# ENCODER_BUFFER.net
KiCad netlist of a schematic drawn in EAGLE
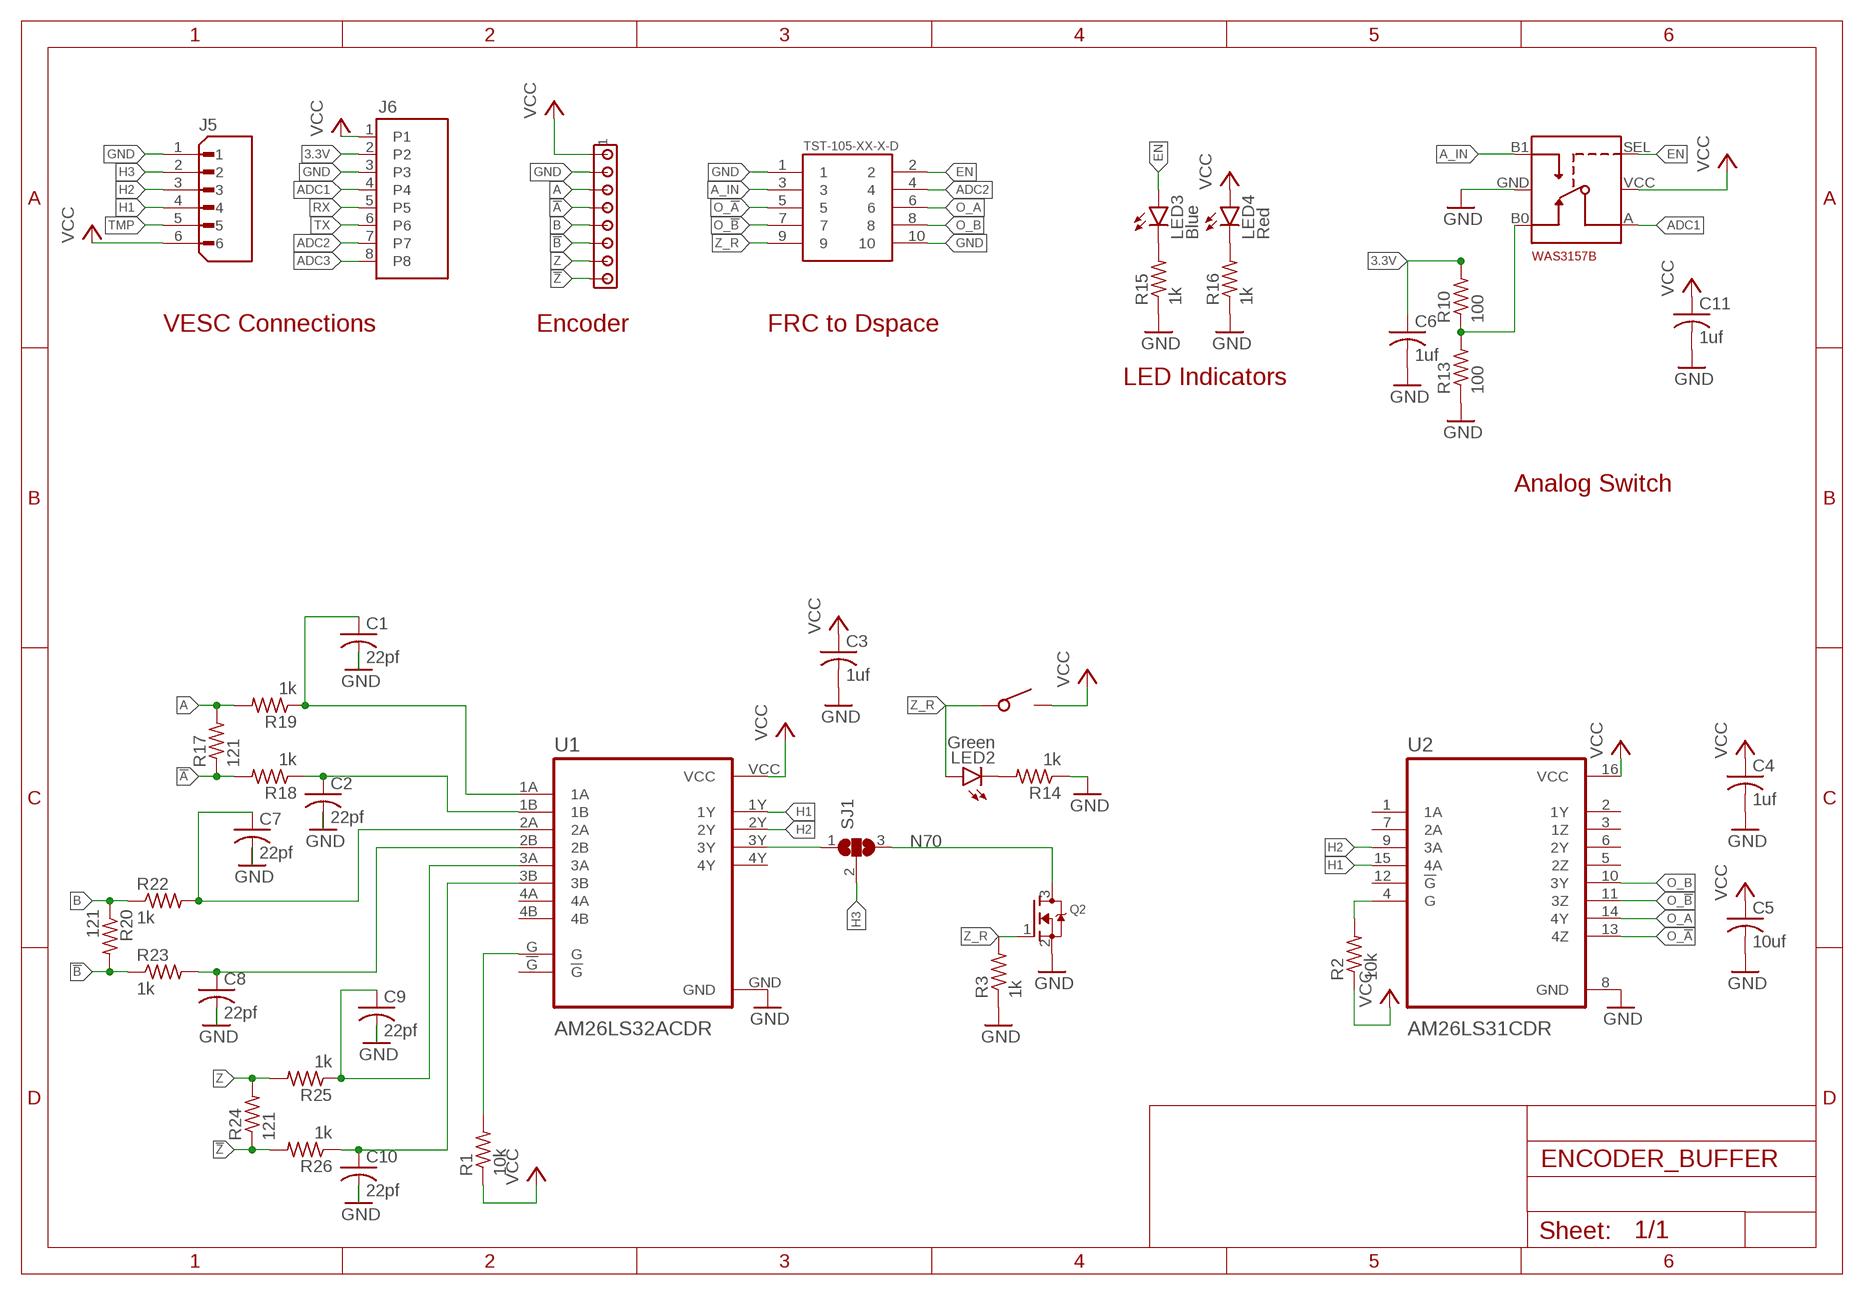
[diagram p0: schematic, sheet 1]

(export (version "E")
  (design (tool "Eeschema 10.0.6"))
  (components
    (comp (ref "C1")
      (value "22pf")
      (footprint "eagle-import:C0402")
      (libsource (lib "eagle-import") (part "C-USC0402"))
    )
    (comp (ref "C2")
      (value "22pf")
      (footprint "eagle-import:C0402")
      (libsource (lib "eagle-import") (part "C-USC0402"))
    )
    (comp (ref "C3")
      (value "1uf")
      (footprint "eagle-import:C0402")
      (libsource (lib "eagle-import") (part "C-USC0402"))
    )
    (comp (ref "C4")
      (value "1uf")
      (footprint "eagle-import:C0402")
      (libsource (lib "eagle-import") (part "C-USC0402"))
    )
    (comp (ref "C5")
      (value "10uf")
      (footprint "eagle-import:C0402")
      (libsource (lib "eagle-import") (part "C-USC0402"))
    )
    (comp (ref "C6")
      (value "1uf")
      (footprint "eagle-import:C0402")
      (libsource (lib "eagle-import") (part "C-USC0402"))
    )
    (comp (ref "C7")
      (value "22pf")
      (footprint "eagle-import:C0402")
      (libsource (lib "eagle-import") (part "C-USC0402"))
    )
    (comp (ref "C8")
      (value "22pf")
      (footprint "eagle-import:C0402")
      (libsource (lib "eagle-import") (part "C-USC0402"))
    )
    (comp (ref "C9")
      (value "22pf")
      (footprint "eagle-import:C0402")
      (libsource (lib "eagle-import") (part "C-USC0402"))
    )
    (comp (ref "C10")
      (value "22pf")
      (footprint "eagle-import:C0402")
      (libsource (lib "eagle-import") (part "C-USC0402"))
    )
    (comp (ref "C11")
      (value "1uf")
      (footprint "eagle-import:C0402")
      (libsource (lib "eagle-import") (part "C-USC0402"))
    )
    (comp (ref "J2")
      (value "TST-105-XX-X-D")
      (footprint "eagle-import:TST-105-XX-X-D")
      (fields (field (name "MF") "Samtec") (field (name "MP") "TST-105-03-S-D"))
      (libsource (lib "eagle-import") (part "TST-105-XX-X-D"))
    )
    (comp (ref "J3")
      (value "MTA08-100")
      (footprint "eagle-import:10X08MTA")
      (libsource (lib "eagle-import") (part "MTA08-100"))
    )
    (comp (ref "J5")
      (value "B6B-PH-K-S(LF)(SN)")
      (footprint "eagle-import:JST_B6B-PH-K-S(LF)(SN)")
      (fields (field (name "MF") "JST Sales"))
      (libsource (lib "eagle-import") (part "B6B-PH-K-S(LF)(SN)"))
    )
    (comp (ref "J6")
      (value "B8B-PH-K-S(LF)(SN)")
      (footprint "eagle-import:JST_B8B-PH-K-S(LF)(SN)")
      (fields (field (name "MF") "JST Sales"))
      (libsource (lib "eagle-import") (part "B8B-PH-K-S(LF)(SN)"))
    )
    (comp (ref "LED2")
      (value "Green")
      (footprint "eagle-import:CHIPLED_0603")
      (libsource (lib "eagle-import") (part "LEDCHIPLED_0603"))
    )
    (comp (ref "LED3")
      (value "Blue")
      (footprint "eagle-import:CHIPLED_0603")
      (libsource (lib "eagle-import") (part "LEDCHIPLED_0603"))
    )
    (comp (ref "LED4")
      (value "Red")
      (footprint "eagle-import:CHIPLED_0603")
      (libsource (lib "eagle-import") (part "LEDCHIPLED_0603"))
    )
    (comp (ref "Q2")
      (value "MOSFET-NREFLOW")
      (footprint "eagle-import:SOT23")
      (libsource (lib "eagle-import") (part "MOSFET-NREFLOW"))
    )
    (comp (ref "R1")
      (value "10k")
      (footprint "eagle-import:R0402")
      (libsource (lib "eagle-import") (part "R-US_R0402"))
    )
    (comp (ref "R2")
      (value "10k")
      (footprint "eagle-import:R0402")
      (libsource (lib "eagle-import") (part "R-US_R0402"))
    )
    (comp (ref "R3")
      (value "1k")
      (footprint "eagle-import:R0402")
      (libsource (lib "eagle-import") (part "R-US_R0402"))
    )
    (comp (ref "R10")
      (value "100")
      (footprint "eagle-import:R0402")
      (libsource (lib "eagle-import") (part "R-US_R0402"))
    )
    (comp (ref "R13")
      (value "100")
      (footprint "eagle-import:R0402")
      (libsource (lib "eagle-import") (part "R-US_R0402"))
    )
    (comp (ref "R14")
      (value "1k")
      (footprint "eagle-import:R0402")
      (libsource (lib "eagle-import") (part "R-US_R0402"))
    )
    (comp (ref "R15")
      (value "1k")
      (footprint "eagle-import:R0402")
      (libsource (lib "eagle-import") (part "R-US_R0402"))
    )
    (comp (ref "R16")
      (value "1k")
      (footprint "eagle-import:R0402")
      (libsource (lib "eagle-import") (part "R-US_R0402"))
    )
    (comp (ref "R17")
      (value "121")
      (footprint "eagle-import:R0402")
      (libsource (lib "eagle-import") (part "R-US_R0402"))
    )
    (comp (ref "R18")
      (value "1k")
      (footprint "eagle-import:R0402")
      (libsource (lib "eagle-import") (part "R-US_R0402"))
    )
    (comp (ref "R19")
      (value "1k")
      (footprint "eagle-import:R0402")
      (libsource (lib "eagle-import") (part "R-US_R0402"))
    )
    (comp (ref "R20")
      (value "121")
      (footprint "eagle-import:R0402")
      (libsource (lib "eagle-import") (part "R-US_R0402"))
    )
    (comp (ref "R22")
      (value "1k")
      (footprint "eagle-import:R0402")
      (libsource (lib "eagle-import") (part "R-US_R0402"))
    )
    (comp (ref "R23")
      (value "1k")
      (footprint "eagle-import:R0402")
      (libsource (lib "eagle-import") (part "R-US_R0402"))
    )
    (comp (ref "R24")
      (value "121")
      (footprint "eagle-import:R0402")
      (libsource (lib "eagle-import") (part "R-US_R0402"))
    )
    (comp (ref "R25")
      (value "1k")
      (footprint "eagle-import:R0402")
      (libsource (lib "eagle-import") (part "R-US_R0402"))
    )
    (comp (ref "R26")
      (value "1k")
      (footprint "eagle-import:R0402")
      (libsource (lib "eagle-import") (part "R-US_R0402"))
    )
    (comp (ref "SJ1")
      (value "SJ2W")
      (footprint "eagle-import:SJ_2")
      (libsource (lib "eagle-import") (part "SJ2W"))
    )
    (comp (ref "U$1")
      (value "TS-1088-AR02016")
      (footprint "eagle-import:SMD")
      (libsource (lib "eagle-import") (part "TS-1088-AR02016"))
    )
    (comp (ref "U1")
      (value "AM26LS32ACDR")
      (footprint "eagle-import:SOIC127P600X175-16N")
      (fields (field (name "MF") "Texas Instruments") (field (name "MP") "AM26LS31CDR"))
      (libsource (lib "eagle-import") (part "AM26LS32ACDR"))
    )
    (comp (ref "U2")
      (value "AM26LS31CDR")
      (footprint "eagle-import:SOIC127P600X175-16N")
      (fields (field (name "MF") "Texas Instruments"))
      (libsource (lib "eagle-import") (part "AM26LS31CDR"))
    )
    (comp (ref "U3")
      (value "WAS3157BUMT6")
      (footprint "eagle-import:UMT6")
      (fields (field (name "MF") "Rohm") (field (name "MP") "UMH3N"))
      (libsource (lib "eagle-import") (part "WAS3157BUMT6"))
    )
  )
  (nets
    (net (code "1") (name "/N70") (class "Default")
      (node (ref "Q2") (pin "3") (pinfunction "D_3") (pintype "bidirectional"))
      (node (ref "SJ1") (pin "3") (pinfunction "3_3") (pintype "passive"))
    )
    (net (code "2") (name "/O_~{A}") (class "Default")
      (node (ref "J2") (pin "5") (pinfunction "5_5") (pintype "bidirectional"))
      (node (ref "U2") (pin "13") (pinfunction "4Z_13") (pintype "output"))
    )
    (net (code "3") (name "/O_~{B}") (class "Default")
      (node (ref "J2") (pin "7") (pinfunction "7_7") (pintype "bidirectional"))
      (node (ref "U2") (pin "11") (pinfunction "3Z_11") (pintype "output"))
    )
    (net (code "4") (name "/~{A}") (class "Default")
      (node (ref "J3") (pin "4") (pinfunction "4_4") (pintype "passive"))
      (node (ref "R17") (pin "1") (pinfunction "1_1") (pintype "passive"))
      (node (ref "R18") (pin "2") (pinfunction "2_2") (pintype "passive"))
    )
    (net (code "5") (name "/~{B}") (class "Default")
      (node (ref "J3") (pin "6") (pinfunction "6_6") (pintype "passive"))
      (node (ref "R20") (pin "2") (pinfunction "2_2") (pintype "passive"))
      (node (ref "R23") (pin "1") (pinfunction "1_1") (pintype "passive"))
    )
    (net (code "6") (name "/~{Z}") (class "Default")
      (node (ref "J3") (pin "8") (pinfunction "8_8") (pintype "passive"))
      (node (ref "R24") (pin "1") (pinfunction "1_1") (pintype "passive"))
      (node (ref "R26") (pin "2") (pinfunction "2_2") (pintype "passive"))
    )
    (net (code "7") (name "3.3V") (class "Default")
      (node (ref "C6") (pin "1") (pinfunction "1_1") (pintype "passive"))
      (node (ref "J6") (pin "2") (pinfunction "P2_2") (pintype "passive"))
      (node (ref "R10") (pin "2") (pinfunction "2_2") (pintype "passive"))
    )
    (net (code "8") (name "A") (class "Default")
      (node (ref "J3") (pin "3") (pinfunction "3_3") (pintype "passive"))
      (node (ref "R17") (pin "2") (pinfunction "2_2") (pintype "passive"))
      (node (ref "R19") (pin "2") (pinfunction "2_2") (pintype "passive"))
    )
    (net (code "9") (name "ADC1") (class "Default")
      (node (ref "J6") (pin "4") (pinfunction "P4_4") (pintype "passive"))
      (node (ref "U3") (pin "A") (pinfunction "A_A") (pintype "output"))
    )
    (net (code "10") (name "ADC2") (class "Default")
      (node (ref "J2") (pin "4") (pinfunction "4_4") (pintype "bidirectional"))
      (node (ref "J6") (pin "7") (pinfunction "P7_7") (pintype "passive"))
    )
    (net (code "11") (name "ADC3") (class "Default")
      (node (ref "J6") (pin "8") (pinfunction "P8_8") (pintype "passive"))
    )
    (net (code "12") (name "A_IN") (class "Default")
      (node (ref "J2") (pin "3") (pinfunction "3_3") (pintype "bidirectional"))
      (node (ref "U3") (pin "B1") (pinfunction "B1_B1") (pintype "output"))
    )
    (net (code "13") (name "B") (class "Default")
      (node (ref "J3") (pin "5") (pinfunction "5_5") (pintype "passive"))
      (node (ref "R20") (pin "1") (pinfunction "1_1") (pintype "passive"))
      (node (ref "R22") (pin "1") (pinfunction "1_1") (pintype "passive"))
    )
    (net (code "14") (name "EN") (class "Default")
      (node (ref "J2") (pin "2") (pinfunction "2_2") (pintype "bidirectional"))
      (node (ref "LED3") (pin "A") (pinfunction "A_A") (pintype "passive"))
      (node (ref "U3") (pin "SEL") (pinfunction "SEL_SEL") (pintype "input"))
    )
    (net (code "15") (name "GND") (class "Default")
      (node (ref "C1") (pin "2") (pinfunction "2_2") (pintype "passive"))
      (node (ref "C10") (pin "2") (pinfunction "2_2") (pintype "passive"))
      (node (ref "C11") (pin "2") (pinfunction "2_2") (pintype "passive"))
      (node (ref "C2") (pin "2") (pinfunction "2_2") (pintype "passive"))
      (node (ref "C3") (pin "2") (pinfunction "2_2") (pintype "passive"))
      (node (ref "C4") (pin "2") (pinfunction "2_2") (pintype "passive"))
      (node (ref "C5") (pin "2") (pinfunction "2_2") (pintype "passive"))
      (node (ref "C6") (pin "2") (pinfunction "2_2") (pintype "passive"))
      (node (ref "C7") (pin "2") (pinfunction "2_2") (pintype "passive"))
      (node (ref "C8") (pin "2") (pinfunction "2_2") (pintype "passive"))
      (node (ref "C9") (pin "2") (pinfunction "2_2") (pintype "passive"))
      (node (ref "J2") (pin "1") (pinfunction "1_1") (pintype "bidirectional"))
      (node (ref "J2") (pin "10") (pinfunction "10_10") (pintype "bidirectional"))
      (node (ref "J3") (pin "2") (pinfunction "2_2") (pintype "passive"))
      (node (ref "J5") (pin "1") (pinfunction "1_1") (pintype "passive"))
      (node (ref "J6") (pin "3") (pinfunction "P3_3") (pintype "passive"))
      (node (ref "Q2") (pin "2") (pinfunction "S_2") (pintype "bidirectional"))
      (node (ref "R13") (pin "1") (pinfunction "1_1") (pintype "passive"))
      (node (ref "R14") (pin "1") (pinfunction "1_1") (pintype "passive"))
      (node (ref "R15") (pin "1") (pinfunction "1_1") (pintype "passive"))
      (node (ref "R16") (pin "1") (pinfunction "1_1") (pintype "passive"))
      (node (ref "R3") (pin "1") (pinfunction "1_1") (pintype "passive"))
      (node (ref "U1") (pin "GND") (pinfunction "GND_GND") (pintype "power_in"))
      (node (ref "U2") (pin "8") (pinfunction "GND_8") (pintype "power_in"))
      (node (ref "U3") (pin "GND") (pinfunction "GND_GND") (pintype "input"))
    )
    (net (code "16") (name "H1") (class "Default")
      (node (ref "J5") (pin "4") (pinfunction "4_4") (pintype "passive"))
      (node (ref "U1") (pin "1Y") (pinfunction "1Y_1Y") (pintype "bidirectional"))
      (node (ref "U2") (pin "15") (pinfunction "4A_15") (pintype "input"))
    )
    (net (code "17") (name "H2") (class "Default")
      (node (ref "J5") (pin "3") (pinfunction "3_3") (pintype "passive"))
      (node (ref "U1") (pin "2Y") (pinfunction "2Y_2Y") (pintype "bidirectional"))
      (node (ref "U2") (pin "9") (pinfunction "3A_9") (pintype "input"))
    )
    (net (code "18") (name "H3") (class "Default")
      (node (ref "J5") (pin "2") (pinfunction "2_2") (pintype "passive"))
      (node (ref "SJ1") (pin "2") (pinfunction "2_2") (pintype "passive"))
    )
    (net (code "19") (name "Net-(C1-Pad1)") (class "Default")
      (node (ref "C1") (pin "1") (pinfunction "1_1") (pintype "passive"))
      (node (ref "R19") (pin "1") (pinfunction "1_1") (pintype "passive"))
      (node (ref "U1") (pin "1A") (pinfunction "1A_1A") (pintype "bidirectional"))
    )
    (net (code "20") (name "Net-(C2-Pad1)") (class "Default")
      (node (ref "C2") (pin "1") (pinfunction "1_1") (pintype "passive"))
      (node (ref "R18") (pin "1") (pinfunction "1_1") (pintype "passive"))
      (node (ref "U1") (pin "1B") (pinfunction "1B_1B") (pintype "bidirectional"))
    )
    (net (code "21") (name "Net-(C7-Pad1)") (class "Default")
      (node (ref "C7") (pin "1") (pinfunction "1_1") (pintype "passive"))
      (node (ref "R22") (pin "2") (pinfunction "2_2") (pintype "passive"))
      (node (ref "U1") (pin "2A") (pinfunction "2A_2A") (pintype "bidirectional"))
    )
    (net (code "22") (name "Net-(C8-Pad1)") (class "Default")
      (node (ref "C8") (pin "1") (pinfunction "1_1") (pintype "passive"))
      (node (ref "R23") (pin "2") (pinfunction "2_2") (pintype "passive"))
      (node (ref "U1") (pin "2B") (pinfunction "2B_2B") (pintype "bidirectional"))
    )
    (net (code "23") (name "Net-(C9-Pad1)") (class "Default")
      (node (ref "C9") (pin "1") (pinfunction "1_1") (pintype "passive"))
      (node (ref "R25") (pin "1") (pinfunction "1_1") (pintype "passive"))
      (node (ref "U1") (pin "3A") (pinfunction "3A_3A") (pintype "bidirectional"))
    )
    (net (code "24") (name "Net-(C10-Pad1)") (class "Default")
      (node (ref "C10") (pin "1") (pinfunction "1_1") (pintype "passive"))
      (node (ref "R26") (pin "1") (pinfunction "1_1") (pintype "passive"))
      (node (ref "U1") (pin "3B") (pinfunction "3B_3B") (pintype "bidirectional"))
    )
    (net (code "25") (name "Net-(LED2-PadC)") (class "Default")
      (node (ref "LED2") (pin "C") (pinfunction "C_C") (pintype "passive"))
      (node (ref "R14") (pin "2") (pinfunction "2_2") (pintype "passive"))
    )
    (net (code "26") (name "Net-(LED3-PadC)") (class "Default")
      (node (ref "LED3") (pin "C") (pinfunction "C_C") (pintype "passive"))
      (node (ref "R15") (pin "2") (pinfunction "2_2") (pintype "passive"))
    )
    (net (code "27") (name "Net-(LED4-PadC)") (class "Default")
      (node (ref "LED4") (pin "C") (pinfunction "C_C") (pintype "passive"))
      (node (ref "R16") (pin "2") (pinfunction "2_2") (pintype "passive"))
    )
    (net (code "28") (name "Net-(R1-Pad2)") (class "Default")
      (node (ref "R1") (pin "2") (pinfunction "2_2") (pintype "passive"))
      (node (ref "U1") (pin "G") (pinfunction "G_G") (pintype "input"))
    )
    (net (code "29") (name "Net-(R10-Pad1)") (class "Default")
      (node (ref "R10") (pin "1") (pinfunction "1_1") (pintype "passive"))
      (node (ref "R13") (pin "2") (pinfunction "2_2") (pintype "passive"))
      (node (ref "U3") (pin "B0") (pinfunction "B0_B0") (pintype "input"))
    )
    (net (code "30") (name "Net-(SJ1-Pad1)") (class "Default")
      (node (ref "SJ1") (pin "1") (pinfunction "1_1") (pintype "passive"))
      (node (ref "U1") (pin "3Y") (pinfunction "3Y_3Y") (pintype "bidirectional"))
    )
    (net (code "31") (name "Net-(U2-G)") (class "Default")
      (node (ref "R2") (pin "2") (pinfunction "2_2") (pintype "passive"))
      (node (ref "U2") (pin "4") (pinfunction "G_4") (pintype "input"))
    )
    (net (code "32") (name "O_A") (class "Default")
      (node (ref "J2") (pin "6") (pinfunction "6_6") (pintype "bidirectional"))
      (node (ref "U2") (pin "14") (pinfunction "4Y_14") (pintype "output"))
    )
    (net (code "33") (name "O_B") (class "Default")
      (node (ref "J2") (pin "8") (pinfunction "8_8") (pintype "bidirectional"))
      (node (ref "U2") (pin "10") (pinfunction "3Y_10") (pintype "output"))
    )
    (net (code "34") (name "RX") (class "Default")
      (node (ref "J6") (pin "5") (pinfunction "P5_5") (pintype "passive"))
    )
    (net (code "35") (name "TMP") (class "Default")
      (node (ref "J5") (pin "5") (pinfunction "5_5") (pintype "passive"))
    )
    (net (code "36") (name "TX") (class "Default")
      (node (ref "J6") (pin "6") (pinfunction "P6_6") (pintype "passive"))
    )
    (net (code "37") (name "VCC") (class "Default")
      (node (ref "C11") (pin "1") (pinfunction "1_1") (pintype "passive"))
      (node (ref "C3") (pin "1") (pinfunction "1_1") (pintype "passive"))
      (node (ref "C4") (pin "1") (pinfunction "1_1") (pintype "passive"))
      (node (ref "C5") (pin "1") (pinfunction "1_1") (pintype "passive"))
      (node (ref "J3") (pin "1") (pinfunction "1_1") (pintype "passive"))
      (node (ref "J5") (pin "6") (pinfunction "6_6") (pintype "passive"))
      (node (ref "J6") (pin "1") (pinfunction "P1_1") (pintype "passive"))
      (node (ref "LED4") (pin "A") (pinfunction "A_A") (pintype "passive"))
      (node (ref "R1") (pin "1") (pinfunction "1_1") (pintype "passive"))
      (node (ref "R2") (pin "1") (pinfunction "1_1") (pintype "passive"))
      (node (ref "U$1") (pin "P$2") (pinfunction "P$2_P$2") (pintype "bidirectional"))
      (node (ref "U1") (pin "VCC") (pinfunction "VCC_VCC") (pintype "power_in"))
      (node (ref "U2") (pin "16") (pinfunction "VCC_16") (pintype "power_in"))
      (node (ref "U3") (pin "VCC") (pinfunction "VCC_VCC") (pintype "input"))
    )
    (net (code "38") (name "Z") (class "Default")
      (node (ref "J3") (pin "7") (pinfunction "7_7") (pintype "passive"))
      (node (ref "R24") (pin "2") (pinfunction "2_2") (pintype "passive"))
      (node (ref "R25") (pin "2") (pinfunction "2_2") (pintype "passive"))
    )
    (net (code "39") (name "Z_R") (class "Default")
      (node (ref "J2") (pin "9") (pinfunction "9_9") (pintype "bidirectional"))
      (node (ref "LED2") (pin "A") (pinfunction "A_A") (pintype "passive"))
      (node (ref "Q2") (pin "1") (pinfunction "G_1") (pintype "bidirectional"))
      (node (ref "R3") (pin "2") (pinfunction "2_2") (pintype "passive"))
      (node (ref "U$1") (pin "P$1") (pinfunction "P$1_P$1") (pintype "bidirectional"))
    )
    (net (code "40") (name "unconnected-(U1-Pad4A)") (class "Default")
      (node (ref "U1") (pin "4A") (pinfunction "4A_4A") (pintype "bidirectional"))
    )
    (net (code "41") (name "unconnected-(U1-Pad4B)") (class "Default")
      (node (ref "U1") (pin "4B") (pinfunction "4B_4B") (pintype "bidirectional"))
    )
    (net (code "42") (name "unconnected-(U1-Pad4Y)") (class "Default")
      (node (ref "U1") (pin "4Y") (pinfunction "4Y_4Y") (pintype "bidirectional"))
    )
    (net (code "43") (name "unconnected-(U1-~{G}-Pad!G)") (class "Default")
      (node (ref "U1") (pin "!G") (pinfunction "~{G}_!G") (pintype "input"))
    )
    (net (code "44") (name "unconnected-(U2-1A-Pad1)") (class "Default")
      (node (ref "U2") (pin "1") (pinfunction "1A_1") (pintype "input"))
    )
    (net (code "45") (name "unconnected-(U2-1Y-Pad2)") (class "Default")
      (node (ref "U2") (pin "2") (pinfunction "1Y_2") (pintype "output"))
    )
    (net (code "46") (name "unconnected-(U2-1Z-Pad3)") (class "Default")
      (node (ref "U2") (pin "3") (pinfunction "1Z_3") (pintype "output"))
    )
    (net (code "47") (name "unconnected-(U2-2A-Pad7)") (class "Default")
      (node (ref "U2") (pin "7") (pinfunction "2A_7") (pintype "input"))
    )
    (net (code "48") (name "unconnected-(U2-2Y-Pad6)") (class "Default")
      (node (ref "U2") (pin "6") (pinfunction "2Y_6") (pintype "output"))
    )
    (net (code "49") (name "unconnected-(U2-2Z-Pad5)") (class "Default")
      (node (ref "U2") (pin "5") (pinfunction "2Z_5") (pintype "output"))
    )
    (net (code "50") (name "unconnected-(U2-~{G}-Pad12)") (class "Default")
      (node (ref "U2") (pin "12") (pinfunction "~{G}_12") (pintype "input"))
    )
  )
)
